# Magnetometer.net
KiCad netlist of a schematic drawn in Altium Designer
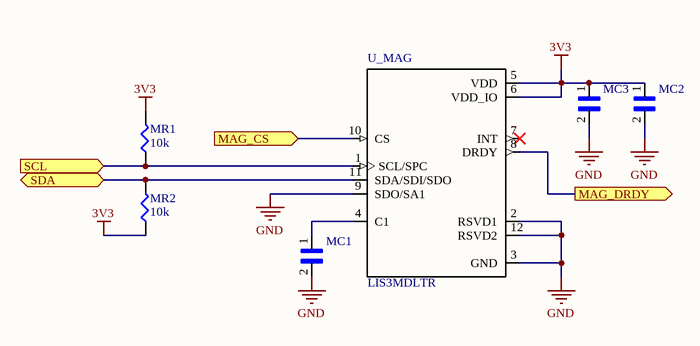
[diagram p0: Magnetometer.SchDoc]

(export (version "E")
  (design (tool "Eeschema 10.0.6"))
  (components
    (comp (ref "MC1")
      (value "GMK107BJ104KAHT")
      (footprint "*CAPC1608X90N")
      (description "CAP , MLCC , 0603, 35V , X5R, 0.1uF10% , T&R")
      (fields (field (name "MF") "Taiyo Yuden") (field (name "DIGI-KEY_PART_NUMBER") "587-3357-1-ND"))
      (libsource (lib "GMK107BJ104KAHT") (part "GMK107BJ104KAHT"))
    )
    (comp (ref "MC2")
      (value "TACL105K016XTA")
      (footprint "*CAPC1608X90")
      (description "Cap Tant Solid 1uF 16V L CASE 10% _1.6 X 0.85 X 0.85mm_ SMD 1608-10 7.5 Ohm 125Â°C Plastic T/R")
      (fields (field (name "DIGI-KEY_PART_NUMBER") "478-4184-1-ND") (field (name "MF") "AVX"))
      (libsource (lib "TACL105K016XTA") (part "TACL105K016XTA"))
    )
    (comp (ref "MC3")
      (value "GMK107BJ104KAHT")
      (footprint "*CAPC1608X90N")
      (description "CAP , MLCC , 0603, 35V , X5R, 0.1uF10% , T&R")
      (fields (field (name "MF") "Taiyo Yuden") (field (name "DIGI-KEY_PART_NUMBER") "587-3357-1-ND"))
      (libsource (lib "GMK107BJ104KAHT") (part "GMK107BJ104KAHT"))
    )
    (comp (ref "MR1")
      (value "10k")
      (footprint "SMD-0603-RES")
      (description "RES SMD 10K OHM 5% 1/4W 0603")
      (fields (field (name "PART NUMBER") "ERJ-PA3J103V") (field (name "DIGI-KEY PART NUMBER") "P10KBZCT-ND"))
      (libsource (lib "Panasonic_ERJ_0603") (part "ERJ-PA3J103V"))
    )
    (comp (ref "MR2")
      (value "10k")
      (footprint "SMD-0603-RES")
      (description "RES SMD 10K OHM 5% 1/4W 0603")
      (fields (field (name "PART NUMBER") "ERJ-PA3J103V") (field (name "DIGI-KEY PART NUMBER") "P10KBZCT-ND"))
      (libsource (lib "Panasonic_ERJ_0603") (part "ERJ-PA3J103V"))
    )
    (comp (ref "U_MAG")
      (value "LIS3MDLTR")
      (footprint "*XDCR_LIS3MDLTR")
      (description "LIS3MDL Series 3 Axis Â±2/Â±8/Â±12/Â±16 g 3.6V High Performance Magnetometer LGA-12")
      (fields (field (name "MF") "STMicroelectronics") (field (name "DIGI-KEY_PART_NUMBER") "497-13892-1-ND"))
      (libsource (lib "LIS3MDLTR") (part "LIS3MDLTR"))
    )
  )
  (nets
    (net (code "1") (name "/MAG_CS") (class "Default")
      (node (ref "U_MAG") (pin "10") (pinfunction "CS_10") (pintype "input"))
    )
    (net (code "2") (name "/MAG_DRDY") (class "Default")
      (node (ref "U_MAG") (pin "8") (pinfunction "DRDY_8") (pintype "output"))
    )
    (net (code "3") (name "/SCL") (class "Default")
      (node (ref "MR1") (pin "1") (pinfunction "1_1") (pintype "passive"))
      (node (ref "U_MAG") (pin "1") (pinfunction "SCL/SPC_1") (pintype "input"))
    )
    (net (code "4") (name "/SDA") (class "Default")
      (node (ref "MR2") (pin "2") (pinfunction "2_2") (pintype "passive"))
      (node (ref "U_MAG") (pin "11") (pinfunction "SDA/SDI/SDO_11") (pintype "bidirectional"))
    )
    (net (code "5") (name "3V3") (class "Default")
      (node (ref "MC2") (pin "1") (pinfunction "1_1") (pintype "passive"))
      (node (ref "MC3") (pin "1") (pinfunction "1_1") (pintype "passive"))
      (node (ref "MR1") (pin "2") (pinfunction "2_2") (pintype "passive"))
      (node (ref "MR2") (pin "1") (pinfunction "1_1") (pintype "passive"))
      (node (ref "U_MAG") (pin "5") (pinfunction "VDD_5") (pintype "power_in"))
      (node (ref "U_MAG") (pin "6") (pinfunction "VDD_IO_6") (pintype "power_in"))
    )
    (net (code "6") (name "GND") (class "Default")
      (node (ref "MC1") (pin "2") (pinfunction "2_2") (pintype "passive"))
      (node (ref "MC2") (pin "2") (pinfunction "2_2") (pintype "passive"))
      (node (ref "MC3") (pin "2") (pinfunction "2_2") (pintype "passive"))
      (node (ref "U_MAG") (pin "12") (pinfunction "RSVD2_12") (pintype "passive"))
      (node (ref "U_MAG") (pin "2") (pinfunction "RSVD1_2") (pintype "passive"))
      (node (ref "U_MAG") (pin "3") (pinfunction "GND_3") (pintype "power_in"))
      (node (ref "U_MAG") (pin "9") (pinfunction "SDO/SA1_9") (pintype "bidirectional"))
    )
    (net (code "7") (name "Net-(U_MAG-C1)") (class "Default")
      (node (ref "MC1") (pin "1") (pinfunction "1_1") (pintype "passive"))
      (node (ref "U_MAG") (pin "4") (pinfunction "C1_4") (pintype "passive"))
    )
    (net (code "8") (name "unconnected-(U_MAG-INT-Pad7)") (class "Default")
      (node (ref "U_MAG") (pin "7") (pinfunction "INT_7") (pintype "output+no_connect"))
    )
  )
)
